# Balance_Circuit.net
KiCad netlist of a schematic drawn in Altium Designer
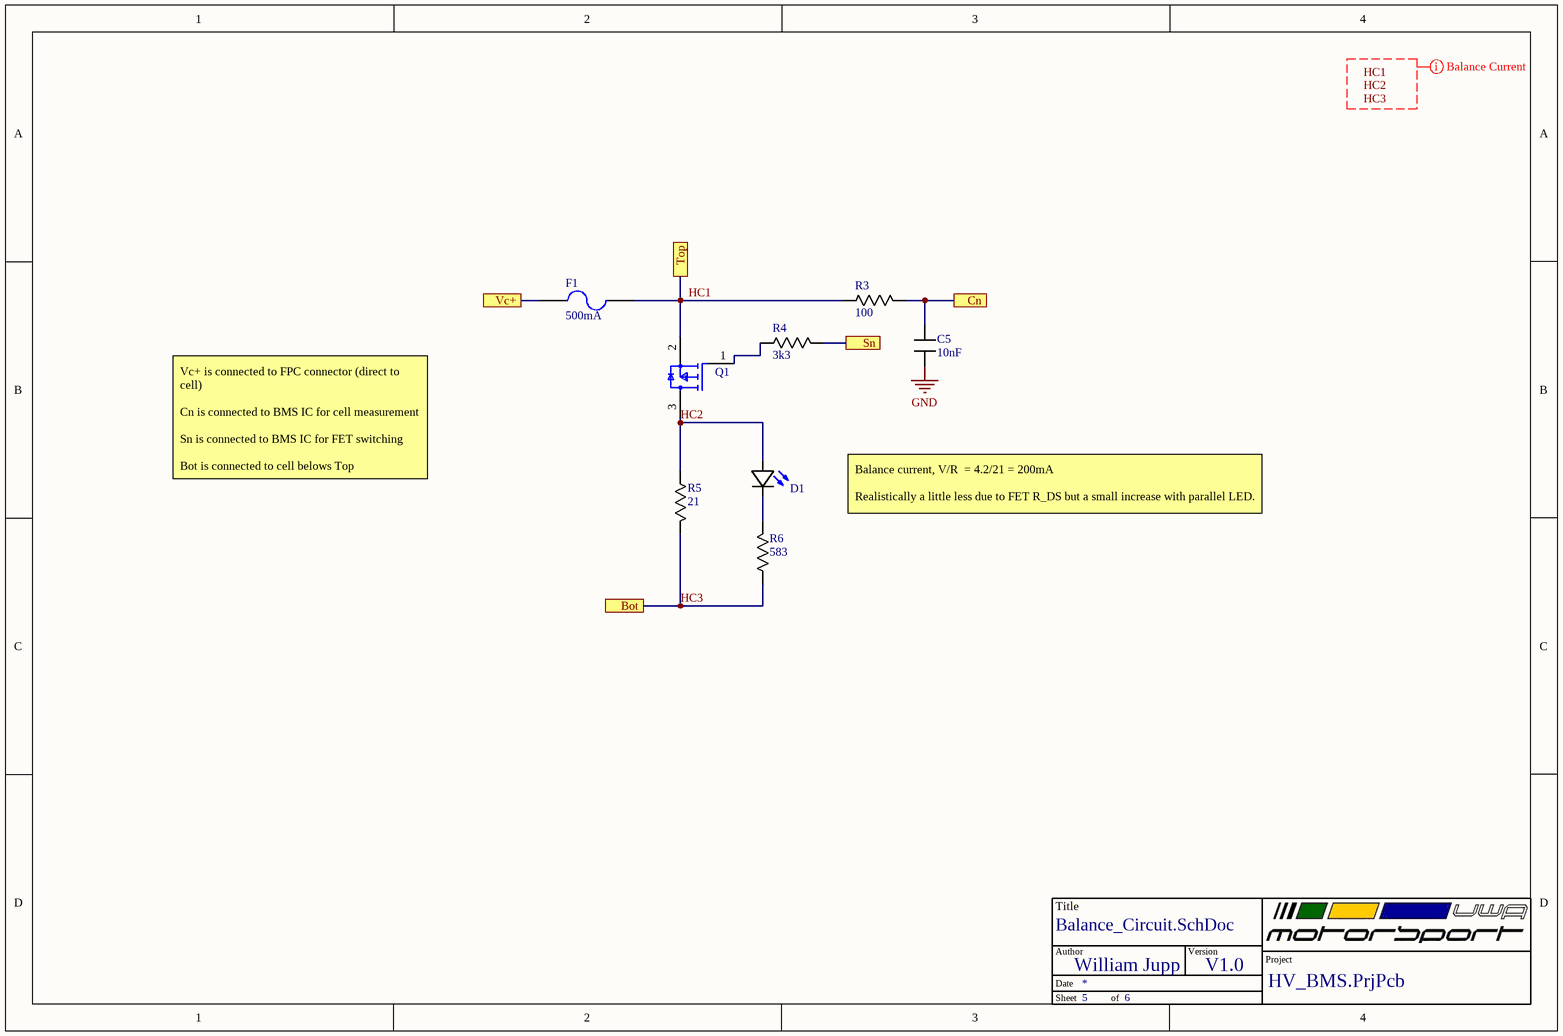
[diagram p0: Balance_Circuit.SchDoc]

(export (version "E")
  (design (tool "Eeschema 10.0.6"))
  (components
    (comp (ref "*") (value "TitleBlock") (libsource (lib "HV_BMS_SCH_LIB") (part "TitleBlock")))
    (comp (ref "C5")
      (value "10nF")
      (footprint "C_0603")
      (description "Capacitor")
      (fields (field (name "Comment") "C"))
      (libsource (lib "Passives") (part "Capacitor"))
    )
    (comp (ref "D1")
      (value "150060BS55040")
      (footprint "LED (0603)")
      (description "LED BLUE DIFFUSED 0603 SMD")
      (fields (field (name "MANUFACTURER") "Wurth Electronics"))
      (libsource (lib "LEDLib") (part "150060BS55040"))
    )
    (comp (ref "F1")
      (value "0466.500NR")
      (footprint "0466.500NR")
      (fields
        (field (name "MANUFACTURER") "Littelfuse")
        (field (name "CURRENT RATING") "500mA")
        (field (name "PUBLISHER") "Altium Limited")
      )
      (libsource (lib "Miscellaneous Devices") (part "Fuse 2"))
    )
    (comp (ref "Q1")
      (value "NX2301P,215")
      (footprint "FP-SOT23-MFG")
      (description "MOSFET P-CH 20V 2A TO-236AB")
      (libsource (lib "Altium Content Vault") (part "882370683d780ecf8f33bea6fe01d97"))
    )
    (comp (ref "R3")
      (value "100")
      (footprint "R-0603")
      (description "Resistor")
      (libsource (lib "Passives") (part "Resistor"))
    )
    (comp (ref "R4")
      (value "3k3")
      (footprint "R-0603")
      (description "Resistor")
      (libsource (lib "Passives") (part "Resistor"))
    )
    (comp (ref "R5")
      (value "21")
      (footprint "R_2512")
      (description "Balance Resistor")
      (fields (field (name "Comment") "CRCW251221R0FKEGHP"))
      (libsource (lib "Passives") (part "Resistor"))
    )
    (comp (ref "R6")
      (value "583")
      (footprint "R-0603")
      (description "Resistor")
      (fields (field (name "Comment") "RT0603DRE07583RL"))
      (libsource (lib "Passives") (part "Resistor"))
    )
  )
  (nets
    (net (code "1") (name "/Cn") (class "Default")
      (node (ref "C5") (pin "2") (pinfunction "2_2") (pintype "passive"))
      (node (ref "R3") (pin "2") (pinfunction "2_2") (pintype "passive"))
    )
    (net (code "2") (name "/HC1") (class "Default")
      (node (ref "F1") (pin "2") (pinfunction "2_2") (pintype "passive"))
      (node (ref "Q1") (pin "2") (pinfunction "S_2") (pintype "passive"))
      (node (ref "R3") (pin "1") (pinfunction "1_1") (pintype "passive"))
    )
    (net (code "3") (name "/HC2") (class "Default")
      (node (ref "D1") (pin "2") (pinfunction "A_2") (pintype "passive"))
      (node (ref "Q1") (pin "3") (pinfunction "D_3") (pintype "passive"))
      (node (ref "R5") (pin "1") (pinfunction "1_1") (pintype "passive"))
    )
    (net (code "4") (name "/HC3") (class "Default")
      (node (ref "R5") (pin "2") (pinfunction "2_2") (pintype "passive"))
      (node (ref "R6") (pin "1") (pinfunction "1_1") (pintype "passive"))
    )
    (net (code "5") (name "/Sn") (class "Default")
      (node (ref "R4") (pin "2") (pinfunction "2_2") (pintype "passive"))
    )
    (net (code "6") (name "/Vc+") (class "Default")
      (node (ref "F1") (pin "1") (pinfunction "1_1") (pintype "passive"))
    )
    (net (code "7") (name "GND") (class "Default")
      (node (ref "C5") (pin "1") (pinfunction "1_1") (pintype "passive"))
    )
    (net (code "8") (name "Net-(D1-K)") (class "Default")
      (node (ref "D1") (pin "1") (pinfunction "K_1") (pintype "passive"))
      (node (ref "R6") (pin "2") (pinfunction "2_2") (pintype "passive"))
    )
    (net (code "9") (name "Net-(Q1-G)") (class "Default")
      (node (ref "Q1") (pin "1") (pinfunction "G_1") (pintype "passive"))
      (node (ref "R4") (pin "1") (pinfunction "1_1") (pintype "passive"))
    )
  )
)
